# UNDP_Shield.net
KiCad netlist of a schematic drawn in EAGLE
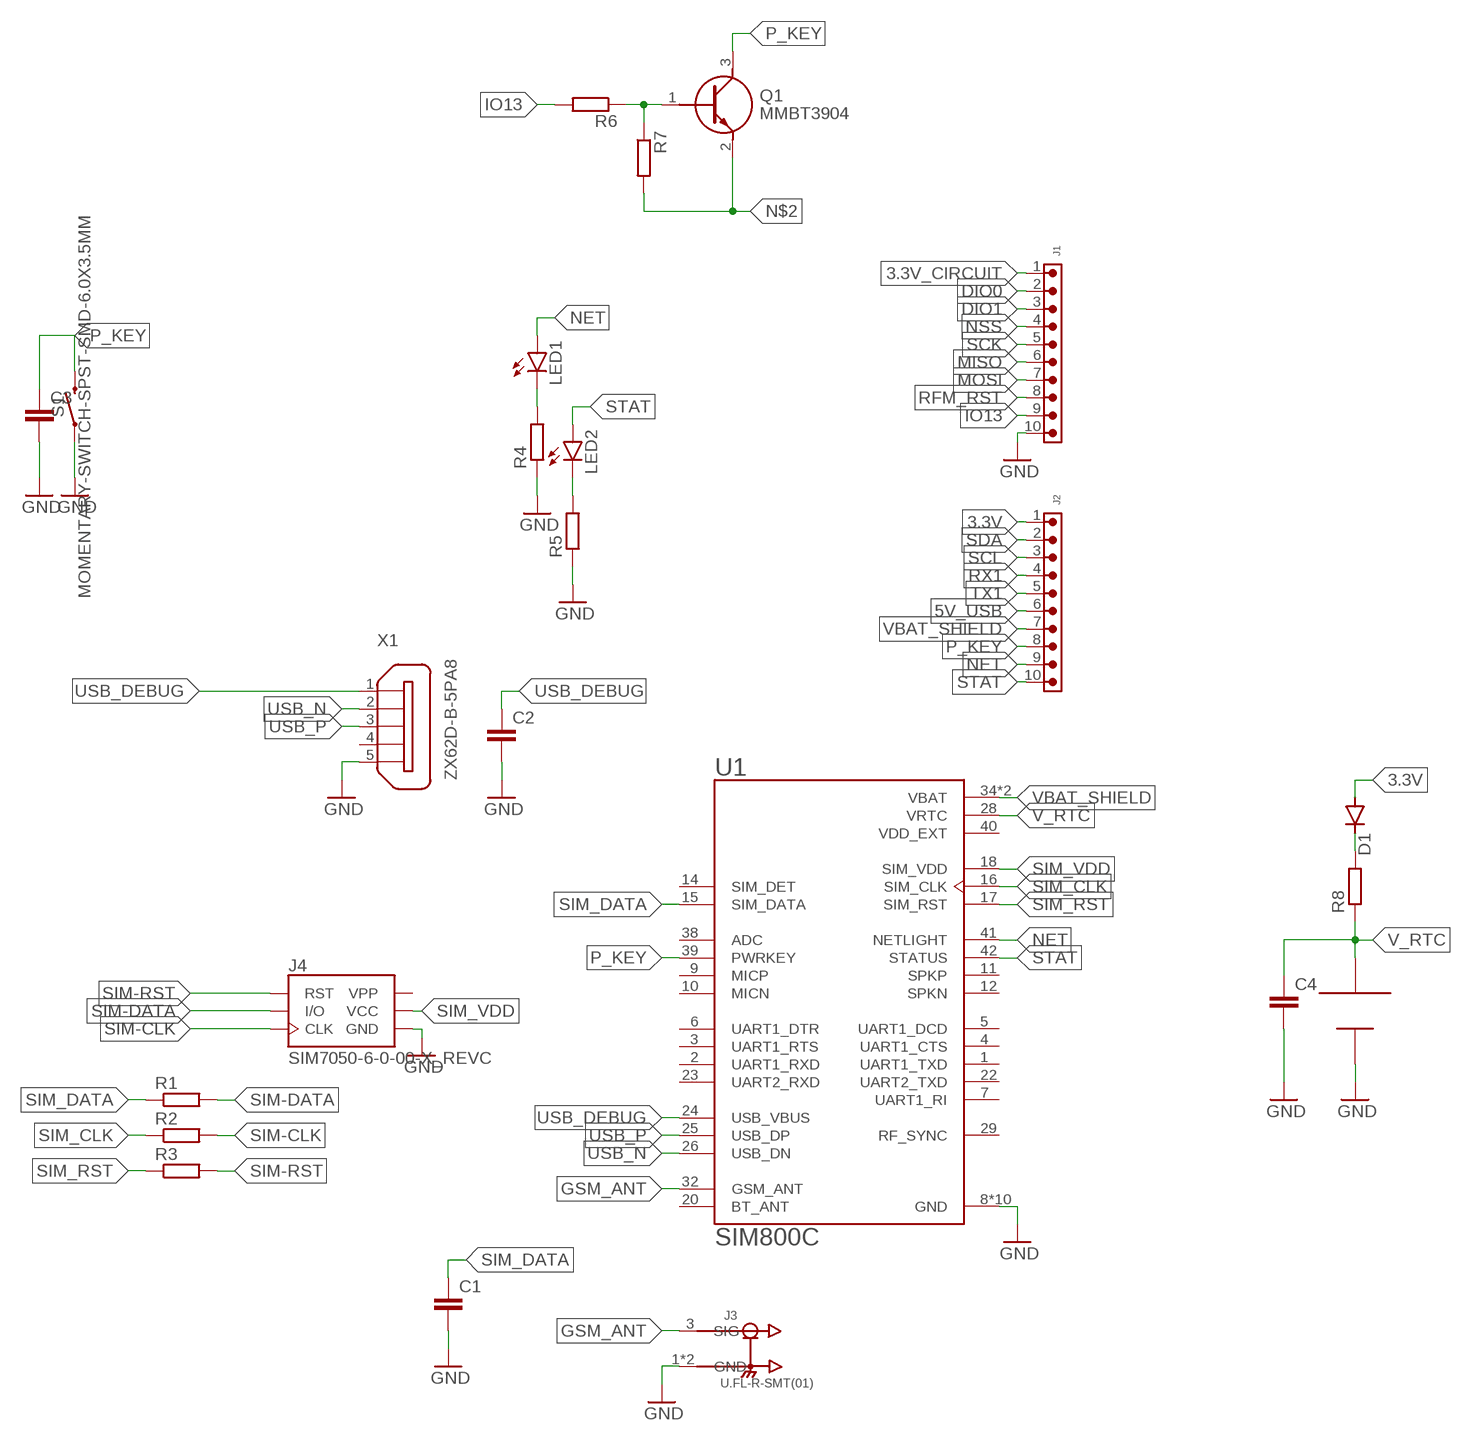
[diagram p0: schematic, sheet 1]

(export (version "E")
  (design (tool "Eeschema 10.0.6"))
  (components
    (comp (ref "C1")
      (value "C-EUC0603")
      (footprint "eagle-import:C0603")
      (libsource (lib "eagle-import") (part "C-EUC0603"))
    )
    (comp (ref "C2")
      (value "C-EUC0603")
      (footprint "eagle-import:C0603")
      (libsource (lib "eagle-import") (part "C-EUC0603"))
    )
    (comp (ref "C3")
      (value "C-EUC0603")
      (footprint "eagle-import:C0603")
      (libsource (lib "eagle-import") (part "C-EUC0603"))
    )
    (comp (ref "C4")
      (value "C-EUC0603")
      (footprint "eagle-import:C0603")
      (libsource (lib "eagle-import") (part "C-EUC0603"))
    )
    (comp (ref "D1")
      (value "DIODE-DO214AC")
      (footprint "eagle-import:DO214AC")
      (libsource (lib "eagle-import") (part "DIODE-DO214AC"))
    )
    (comp (ref "J1")
      (value "6200XX11121_62001011121")
      (footprint "eagle-import:62001011121")
      (libsource (lib "eagle-import") (part "6200XX11121_62001011121"))
    )
    (comp (ref "J2")
      (value "6200XX11121_62001011121")
      (footprint "eagle-import:62001011121")
      (libsource (lib "eagle-import") (part "6200XX11121_62001011121"))
    )
    (comp (ref "J3")
      (value "U.FL-R-SMT(01)")
      (footprint "eagle-import:HRS_U.FL-R-SMT(01)")
      (fields (field (name "MF") "Hirose"))
      (libsource (lib "eagle-import") (part "U.FL-R-SMT(01)"))
    )
    (comp (ref "J4")
      (value "SIM7050-6-0-00-X_REVC")
      (footprint "eagle-import:GCT_SIM7050-6-0-00-X_REVC")
      (fields (field (name "MF") "Global Connector Technology") (field (name "MP") "SIM7050-6-0-00-A"))
      (libsource (lib "eagle-import") (part "SIM7050-6-0-00-X_REVC"))
    )
    (comp (ref "LED1")
      (value "LEDCHIP-LED0805")
      (footprint "eagle-import:CHIP-LED0805")
      (libsource (lib "eagle-import") (part "LEDCHIP-LED0805"))
    )
    (comp (ref "LED2")
      (value "LEDCHIP-LED0805")
      (footprint "eagle-import:CHIP-LED0805")
      (libsource (lib "eagle-import") (part "LEDCHIP-LED0805"))
    )
    (comp (ref "Q1")
      (value "MMBT3904")
      (footprint "eagle-import:SOT95P240X120-3N")
      (fields (field (name "MOUSER_PART_NUMBER") "512-MMBT3904"))
      (libsource (lib "eagle-import") (part "MMBT3904"))
    )
    (comp (ref "R1")
      (value "R-EU_R0603")
      (footprint "eagle-import:R0603")
      (libsource (lib "eagle-import") (part "R-EU_R0603"))
    )
    (comp (ref "R2")
      (value "R-EU_R0603")
      (footprint "eagle-import:R0603")
      (libsource (lib "eagle-import") (part "R-EU_R0603"))
    )
    (comp (ref "R3")
      (value "R-EU_R0603")
      (footprint "eagle-import:R0603")
      (libsource (lib "eagle-import") (part "R-EU_R0603"))
    )
    (comp (ref "R4")
      (value "R-EU_R0603")
      (footprint "eagle-import:R0603")
      (libsource (lib "eagle-import") (part "R-EU_R0603"))
    )
    (comp (ref "R5")
      (value "R-EU_R0603")
      (footprint "eagle-import:R0603")
      (libsource (lib "eagle-import") (part "R-EU_R0603"))
    )
    (comp (ref "R6")
      (value "R-EU_R0603")
      (footprint "eagle-import:R0603")
      (libsource (lib "eagle-import") (part "R-EU_R0603"))
    )
    (comp (ref "R7")
      (value "R-EU_R0603")
      (footprint "eagle-import:R0603")
      (libsource (lib "eagle-import") (part "R-EU_R0603"))
    )
    (comp (ref "R8")
      (value "R-EU_R0603")
      (footprint "eagle-import:R0603")
      (libsource (lib "eagle-import") (part "R-EU_R0603"))
    )
    (comp (ref "S1")
      (value "MOMENTARY-SWITCH-SPST-SMD-6.0X3.5MM")
      (footprint "eagle-import:TACTILE_SWITCH_SMD_6.0X3.5MM")
      (libsource (lib "eagle-import") (part "MOMENTARY-SWITCH-SPST-SMD-6.0X3.5MM"))
    )
    (comp (ref "U$1")
      (value "MS621FE")
      (footprint "eagle-import:MS621FE")
      (libsource (lib "eagle-import") (part "MS621FE"))
    )
    (comp (ref "U1")
      (value "SIM800C")
      (footprint "eagle-import:LCC110P1570X1760X250-42N")
      (fields (field (name "MF") "Simcom"))
      (libsource (lib "eagle-import") (part "SIM800C"))
    )
    (comp (ref "X1")
      (value "ZX62D-B-5PA8")
      (footprint "eagle-import:ZX62D-B-5PA8")
      (fields (field (name "MF") "Hirose"))
      (libsource (lib "eagle-import") (part "ZX62D-B-5PA8"))
    )
  )
  (nets
    (net (code "1") (name "/VDD_EXT") (class "Default")
      (node (ref "U1") (pin "40") (pinfunction "VDD_EXT_40") (pintype "power_in"))
    )
    (net (code "2") (name "/VPP") (class "Default")
      (node (ref "J4") (pin "C6") (pinfunction "VPP_C6") (pintype "power_in"))
    )
    (net (code "3") (name "3.3V") (class "Default")
      (node (ref "D1") (pin "A") (pinfunction "A_A") (pintype "passive"))
      (node (ref "J2") (pin "1") (pinfunction "1_1") (pintype "passive"))
    )
    (net (code "4") (name "3.3V_CIRCUIT") (class "Default")
      (node (ref "J1") (pin "1") (pinfunction "1_1") (pintype "passive"))
    )
    (net (code "5") (name "5V_USB") (class "Default")
      (node (ref "J2") (pin "6") (pinfunction "6_6") (pintype "passive"))
    )
    (net (code "6") (name "DIO0") (class "Default")
      (node (ref "J1") (pin "2") (pinfunction "2_2") (pintype "passive"))
    )
    (net (code "7") (name "DIO1") (class "Default")
      (node (ref "J1") (pin "3") (pinfunction "3_3") (pintype "passive"))
    )
    (net (code "8") (name "GND") (class "Default")
      (node (ref "C1") (pin "2") (pinfunction "2_2") (pintype "passive"))
      (node (ref "C2") (pin "2") (pinfunction "2_2") (pintype "passive"))
      (node (ref "C3") (pin "2") (pinfunction "2_2") (pintype "passive"))
      (node (ref "C4") (pin "2") (pinfunction "2_2") (pintype "passive"))
      (node (ref "J1") (pin "10") (pinfunction "10_10") (pintype "passive"))
      (node (ref "J3") (pin "1") (pinfunction "GND_1") (pintype "passive"))
      (node (ref "J3") (pin "2") (pinfunction "GND_2") (pintype "passive"))
      (node (ref "J4") (pin "C5") (pinfunction "GND_C5") (pintype "power_in"))
      (node (ref "R4") (pin "1") (pinfunction "1_1") (pintype "passive"))
      (node (ref "R5") (pin "1") (pinfunction "1_1") (pintype "passive"))
      (node (ref "S1") (pin "1") (pinfunction "1_1") (pintype "passive"))
      (node (ref "U$1") (pin "V-") (pinfunction "V-_V-") (pintype "bidirectional"))
      (node (ref "U1") (pin "13") (pinfunction "GND_13") (pintype "power_in"))
      (node (ref "U1") (pin "19") (pinfunction "GND_19") (pintype "power_in"))
      (node (ref "U1") (pin "21") (pinfunction "GND_21") (pintype "power_in"))
      (node (ref "U1") (pin "27") (pinfunction "GND_27") (pintype "power_in"))
      (node (ref "U1") (pin "30") (pinfunction "GND_30") (pintype "power_in"))
      (node (ref "U1") (pin "31") (pinfunction "GND_31") (pintype "power_in"))
      (node (ref "U1") (pin "33") (pinfunction "GND_33") (pintype "power_in"))
      (node (ref "U1") (pin "36") (pinfunction "GND_36") (pintype "power_in"))
      (node (ref "U1") (pin "37") (pinfunction "GND_37") (pintype "power_in"))
      (node (ref "U1") (pin "8") (pinfunction "GND_8") (pintype "power_in"))
      (node (ref "X1") (pin "5") (pinfunction "5_5") (pintype "passive"))
    )
    (net (code "9") (name "GSM_ANT") (class "Default")
      (node (ref "J3") (pin "3") (pinfunction "SIG_3") (pintype "passive"))
      (node (ref "U1") (pin "32") (pinfunction "GSM_ANT_32") (pintype "bidirectional"))
    )
    (net (code "10") (name "IO13") (class "Default")
      (node (ref "J1") (pin "9") (pinfunction "9_9") (pintype "passive"))
      (node (ref "R6") (pin "2") (pinfunction "2_2") (pintype "passive"))
    )
    (net (code "11") (name "MISO") (class "Default")
      (node (ref "J1") (pin "6") (pinfunction "6_6") (pintype "passive"))
    )
    (net (code "12") (name "MOSI") (class "Default")
      (node (ref "J1") (pin "7") (pinfunction "7_7") (pintype "passive"))
    )
    (net (code "13") (name "N$2") (class "Default")
      (node (ref "Q1") (pin "2") (pinfunction "E_2") (pintype "bidirectional"))
      (node (ref "R7") (pin "2") (pinfunction "2_2") (pintype "passive"))
    )
    (net (code "14") (name "NET") (class "Default")
      (node (ref "J2") (pin "9") (pinfunction "9_9") (pintype "passive"))
      (node (ref "LED1") (pin "A") (pinfunction "A_A") (pintype "passive"))
      (node (ref "U1") (pin "41") (pinfunction "NETLIGHT_41") (pintype "output"))
    )
    (net (code "15") (name "NSS") (class "Default")
      (node (ref "J1") (pin "4") (pinfunction "4_4") (pintype "passive"))
    )
    (net (code "16") (name "Net-(D1-PadC)") (class "Default")
      (node (ref "D1") (pin "C") (pinfunction "C_C") (pintype "passive"))
      (node (ref "R8") (pin "2") (pinfunction "2_2") (pintype "passive"))
    )
    (net (code "17") (name "Net-(LED1-PadC)") (class "Default")
      (node (ref "LED1") (pin "C") (pinfunction "C_C") (pintype "passive"))
      (node (ref "R4") (pin "2") (pinfunction "2_2") (pintype "passive"))
    )
    (net (code "18") (name "Net-(LED2-PadC)") (class "Default")
      (node (ref "LED2") (pin "C") (pinfunction "C_C") (pintype "passive"))
      (node (ref "R5") (pin "2") (pinfunction "2_2") (pintype "passive"))
    )
    (net (code "19") (name "Net-(Q1-B)") (class "Default")
      (node (ref "Q1") (pin "1") (pinfunction "B_1") (pintype "bidirectional"))
      (node (ref "R6") (pin "1") (pinfunction "1_1") (pintype "passive"))
      (node (ref "R7") (pin "1") (pinfunction "1_1") (pintype "passive"))
    )
    (net (code "20") (name "P_KEY") (class "Default")
      (node (ref "C3") (pin "1") (pinfunction "1_1") (pintype "passive"))
      (node (ref "J2") (pin "8") (pinfunction "8_8") (pintype "passive"))
      (node (ref "Q1") (pin "3") (pinfunction "C_3") (pintype "bidirectional"))
      (node (ref "S1") (pin "2") (pinfunction "2_2") (pintype "passive"))
      (node (ref "U1") (pin "39") (pinfunction "PWRKEY_39") (pintype "input"))
    )
    (net (code "21") (name "RFM_RST") (class "Default")
      (node (ref "J1") (pin "8") (pinfunction "8_8") (pintype "passive"))
    )
    (net (code "22") (name "RX1") (class "Default")
      (node (ref "J2") (pin "4") (pinfunction "4_4") (pintype "passive"))
    )
    (net (code "23") (name "SCK") (class "Default")
      (node (ref "J1") (pin "5") (pinfunction "5_5") (pintype "passive"))
    )
    (net (code "24") (name "SCL") (class "Default")
      (node (ref "J2") (pin "3") (pinfunction "3_3") (pintype "passive"))
    )
    (net (code "25") (name "SDA") (class "Default")
      (node (ref "J2") (pin "2") (pinfunction "2_2") (pintype "passive"))
    )
    (net (code "26") (name "SIM-CLK") (class "Default")
      (node (ref "J4") (pin "C3") (pinfunction "CLK_C3") (pintype "bidirectional"))
      (node (ref "R2") (pin "2") (pinfunction "2_2") (pintype "passive"))
    )
    (net (code "27") (name "SIM-DATA") (class "Default")
      (node (ref "J4") (pin "C7") (pinfunction "I/O_C7") (pintype "bidirectional"))
      (node (ref "R1") (pin "2") (pinfunction "2_2") (pintype "passive"))
    )
    (net (code "28") (name "SIM-RST") (class "Default")
      (node (ref "J4") (pin "C2") (pinfunction "RST_C2") (pintype "input"))
      (node (ref "R3") (pin "2") (pinfunction "2_2") (pintype "passive"))
    )
    (net (code "29") (name "SIM_CLK") (class "Default")
      (node (ref "R2") (pin "1") (pinfunction "1_1") (pintype "passive"))
      (node (ref "U1") (pin "16") (pinfunction "SIM_CLK_16") (pintype "output"))
    )
    (net (code "30") (name "SIM_DATA") (class "Default")
      (node (ref "C1") (pin "1") (pinfunction "1_1") (pintype "passive"))
      (node (ref "R1") (pin "1") (pinfunction "1_1") (pintype "passive"))
      (node (ref "U1") (pin "15") (pinfunction "SIM_DATA_15") (pintype "bidirectional"))
    )
    (net (code "31") (name "SIM_RST") (class "Default")
      (node (ref "R3") (pin "1") (pinfunction "1_1") (pintype "passive"))
      (node (ref "U1") (pin "17") (pinfunction "SIM_RST_17") (pintype "output"))
    )
    (net (code "32") (name "SIM_VDD") (class "Default")
      (node (ref "J4") (pin "C1") (pinfunction "VCC_C1") (pintype "power_in"))
      (node (ref "U1") (pin "18") (pinfunction "SIM_VDD_18") (pintype "output"))
    )
    (net (code "33") (name "STAT") (class "Default")
      (node (ref "J2") (pin "10") (pinfunction "10_10") (pintype "passive"))
      (node (ref "LED2") (pin "A") (pinfunction "A_A") (pintype "passive"))
      (node (ref "U1") (pin "42") (pinfunction "STATUS_42") (pintype "output"))
    )
    (net (code "34") (name "TX1") (class "Default")
      (node (ref "J2") (pin "5") (pinfunction "5_5") (pintype "passive"))
    )
    (net (code "35") (name "USB_DEBUG") (class "Default")
      (node (ref "C2") (pin "1") (pinfunction "1_1") (pintype "passive"))
      (node (ref "U1") (pin "24") (pinfunction "USB_VBUS_24") (pintype "input"))
      (node (ref "X1") (pin "1") (pinfunction "1_1") (pintype "passive"))
    )
    (net (code "36") (name "USB_N") (class "Default")
      (node (ref "U1") (pin "26") (pinfunction "USB_DN_26") (pintype "bidirectional"))
      (node (ref "X1") (pin "2") (pinfunction "2_2") (pintype "passive"))
    )
    (net (code "37") (name "USB_P") (class "Default")
      (node (ref "U1") (pin "25") (pinfunction "USB_DP_25") (pintype "bidirectional"))
      (node (ref "X1") (pin "3") (pinfunction "3_3") (pintype "passive"))
    )
    (net (code "38") (name "VBAT_SHIELD") (class "Default")
      (node (ref "J2") (pin "7") (pinfunction "7_7") (pintype "passive"))
      (node (ref "U1") (pin "34") (pinfunction "VBAT_34") (pintype "power_in"))
      (node (ref "U1") (pin "35") (pinfunction "VBAT_35") (pintype "power_in"))
    )
    (net (code "39") (name "V_RTC") (class "Default")
      (node (ref "C4") (pin "1") (pinfunction "1_1") (pintype "passive"))
      (node (ref "R8") (pin "1") (pinfunction "1_1") (pintype "passive"))
      (node (ref "U$1") (pin "V+") (pinfunction "V+_V+") (pintype "bidirectional"))
      (node (ref "U1") (pin "28") (pinfunction "VRTC_28") (pintype "power_in"))
    )
    (net (code "40") (name "unconnected-(U1-ADC-Pad38)") (class "Default")
      (node (ref "U1") (pin "38") (pinfunction "ADC_38") (pintype "input"))
    )
    (net (code "41") (name "unconnected-(U1-BT_ANT-Pad20)") (class "Default")
      (node (ref "U1") (pin "20") (pinfunction "BT_ANT_20") (pintype "bidirectional"))
    )
    (net (code "42") (name "unconnected-(U1-MICN-Pad10)") (class "Default")
      (node (ref "U1") (pin "10") (pinfunction "MICN_10") (pintype "input"))
    )
    (net (code "43") (name "unconnected-(U1-MICP-Pad9)") (class "Default")
      (node (ref "U1") (pin "9") (pinfunction "MICP_9") (pintype "input"))
    )
    (net (code "44") (name "unconnected-(U1-RF_SYNC-Pad29)") (class "Default")
      (node (ref "U1") (pin "29") (pinfunction "RF_SYNC_29") (pintype "output"))
    )
    (net (code "45") (name "unconnected-(U1-SIM_DET-Pad14)") (class "Default")
      (node (ref "U1") (pin "14") (pinfunction "SIM_DET_14") (pintype "input"))
    )
    (net (code "46") (name "unconnected-(U1-SPKN-Pad12)") (class "Default")
      (node (ref "U1") (pin "12") (pinfunction "SPKN_12") (pintype "output"))
    )
    (net (code "47") (name "unconnected-(U1-SPKP-Pad11)") (class "Default")
      (node (ref "U1") (pin "11") (pinfunction "SPKP_11") (pintype "output"))
    )
    (net (code "48") (name "unconnected-(U1-UART1_CTS-Pad4)") (class "Default")
      (node (ref "U1") (pin "4") (pinfunction "UART1_CTS_4") (pintype "output"))
    )
    (net (code "49") (name "unconnected-(U1-UART1_DCD-Pad5)") (class "Default")
      (node (ref "U1") (pin "5") (pinfunction "UART1_DCD_5") (pintype "output"))
    )
    (net (code "50") (name "unconnected-(U1-UART1_DTR-Pad6)") (class "Default")
      (node (ref "U1") (pin "6") (pinfunction "UART1_DTR_6") (pintype "input"))
    )
    (net (code "51") (name "unconnected-(U1-UART1_RI-Pad7)") (class "Default")
      (node (ref "U1") (pin "7") (pinfunction "UART1_RI_7") (pintype "output"))
    )
    (net (code "52") (name "unconnected-(U1-UART1_RTS-Pad3)") (class "Default")
      (node (ref "U1") (pin "3") (pinfunction "UART1_RTS_3") (pintype "input"))
    )
    (net (code "53") (name "unconnected-(U1-UART1_RXD-Pad2)") (class "Default")
      (node (ref "U1") (pin "2") (pinfunction "UART1_RXD_2") (pintype "input"))
    )
    (net (code "54") (name "unconnected-(U1-UART1_TXD-Pad1)") (class "Default")
      (node (ref "U1") (pin "1") (pinfunction "UART1_TXD_1") (pintype "output"))
    )
    (net (code "55") (name "unconnected-(U1-UART2_RXD-Pad23)") (class "Default")
      (node (ref "U1") (pin "23") (pinfunction "UART2_RXD_23") (pintype "input"))
    )
    (net (code "56") (name "unconnected-(U1-UART2_TXD-Pad22)") (class "Default")
      (node (ref "U1") (pin "22") (pinfunction "UART2_TXD_22") (pintype "output"))
    )
    (net (code "57") (name "unconnected-(X1-Pad4)") (class "Default")
      (node (ref "X1") (pin "4") (pinfunction "4_4") (pintype "passive"))
    )
  )
)
